# MRCS-Tortoise-to-MP-Adapter.net
KiCad netlist of a schematic drawn in EAGLE
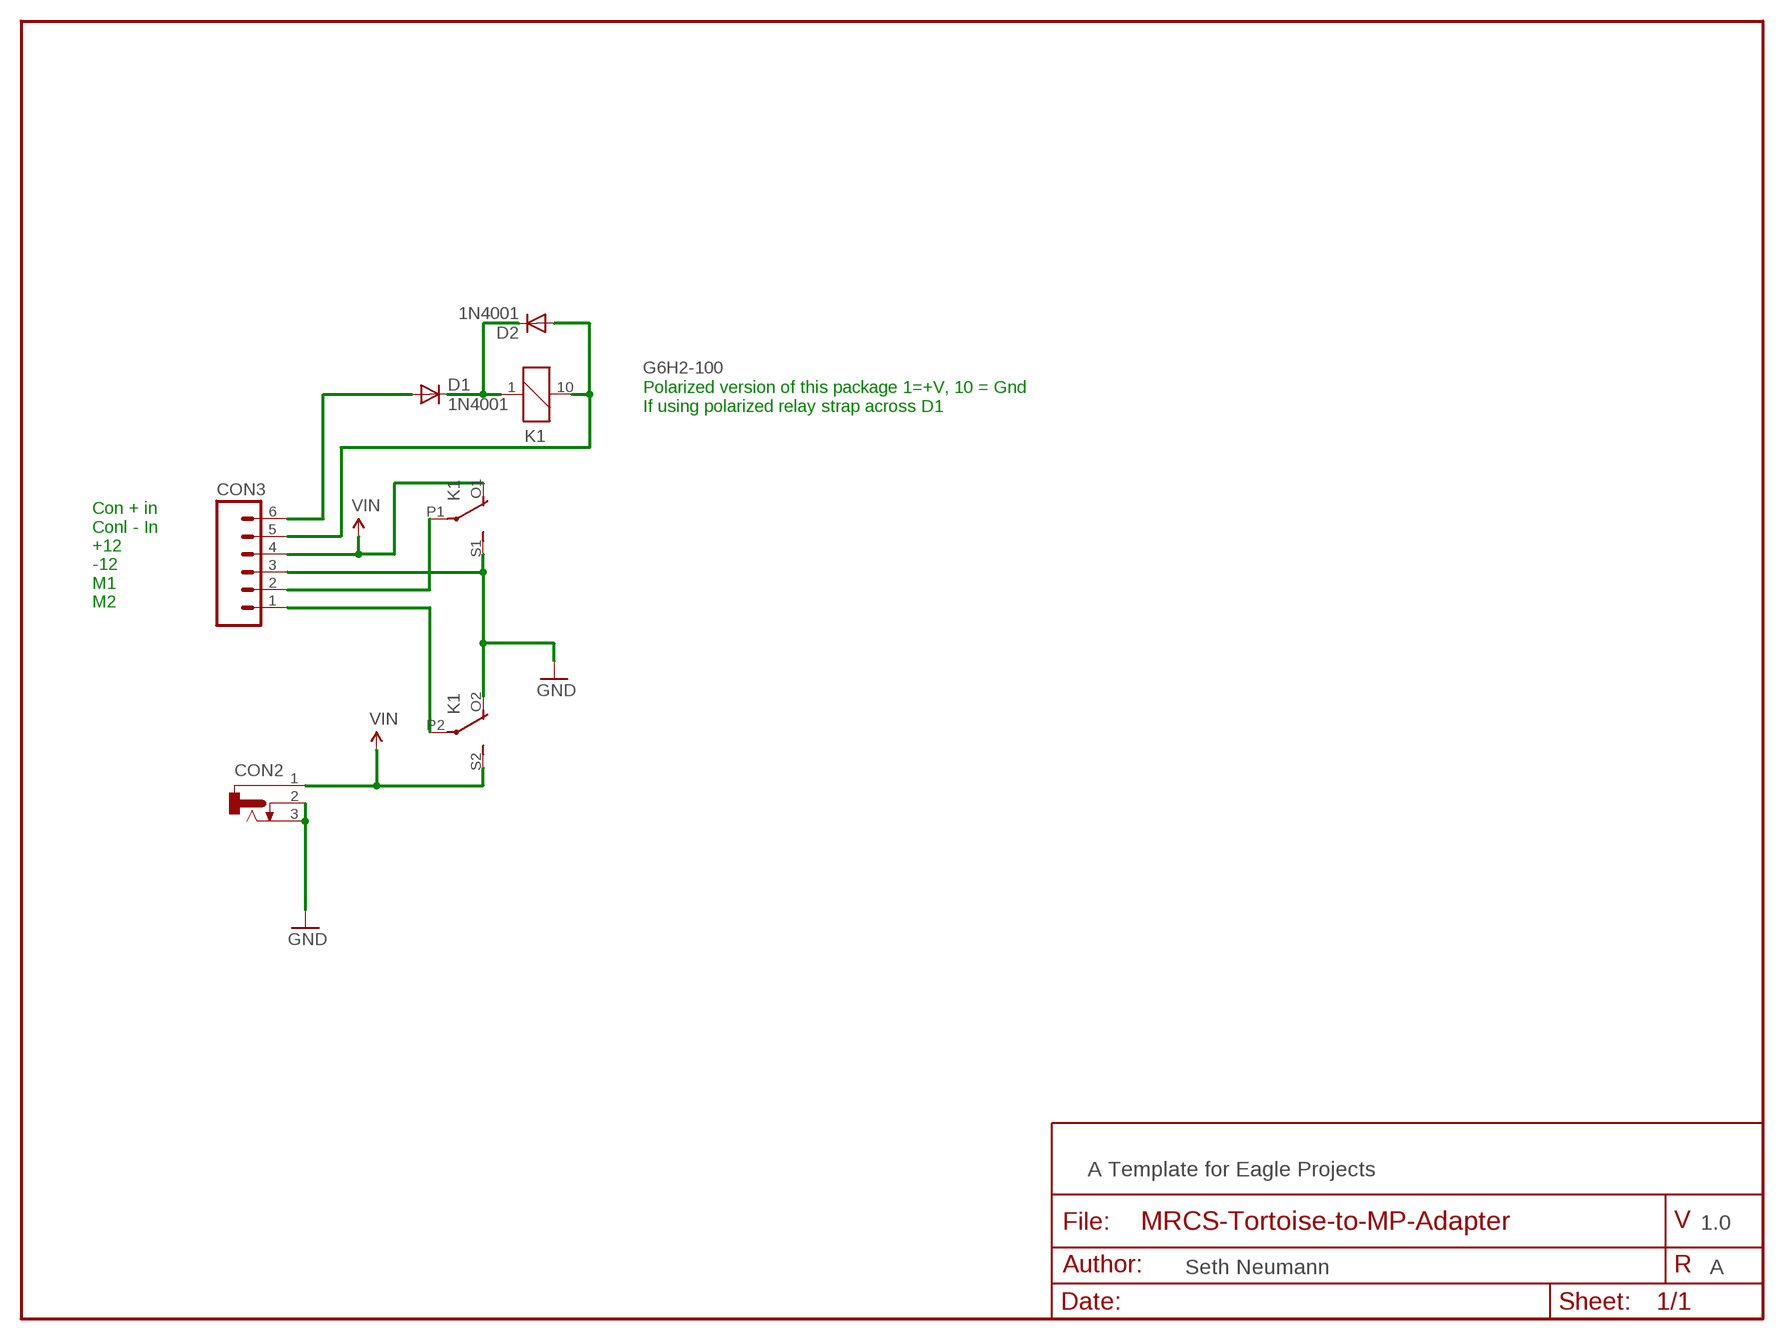
[diagram p0: schematic, sheet 1]

(export (version "E")
  (design (tool "Eeschema 10.0.6"))
  (components
    (comp (ref "CON2")
      (value "CONNECTOR-DC-POWER-RA")
      (footprint "eagle-import:DCJ0202")
      (libsource (lib "eagle-import") (part "CONNECTOR-DC-POWER-RA"))
    )
    (comp (ref "CON3")
      (value "CONNECTOR-M063.5MM-6")
      (footprint "eagle-import:SCREWTERMINAL-3.5MM-6")
      (libsource (lib "eagle-import") (part "CONNECTOR-M063.5MM-6"))
    )
    (comp (ref "D1")
      (value "1N4001")
      (footprint "eagle-import:DIODE-1N4001")
      (libsource (lib "eagle-import") (part "DIODEPTH"))
    )
    (comp (ref "D2")
      (value "1N4001")
      (footprint "eagle-import:DIODE-1N4001")
      (libsource (lib "eagle-import") (part "DIODEPTH"))
    )
    (comp (ref "K1")
      (value "G6H2-100")
      (footprint "eagle-import:G6H2-100")
      (libsource (lib "eagle-import") (part "G6H2-100"))
    )
  )
  (nets
    (net (code "1") (name "GND") (class "Default")
      (node (ref "CON2") (pin "2") (pinfunction "2_2") (pintype "passive"))
      (node (ref "CON2") (pin "3") (pinfunction "3_3") (pintype "passive"))
      (node (ref "CON3") (pin "3") (pinfunction "3_3") (pintype "passive"))
      (node (ref "K1") (pin "O2") (pinfunction "O_O2") (pintype "passive"))
      (node (ref "K1") (pin "S1") (pinfunction "S_S1") (pintype "passive"))
    )
    (net (code "2") (name "Net-(CON3-Pad6)") (class "Default")
      (node (ref "CON3") (pin "6") (pinfunction "6_6") (pintype "passive"))
      (node (ref "D1") (pin "A") (pinfunction "A_A") (pintype "passive"))
    )
    (net (code "3") (name "Net-(D1-PadC)") (class "Default")
      (node (ref "D1") (pin "C") (pinfunction "C_C") (pintype "passive"))
      (node (ref "D2") (pin "C") (pinfunction "C_C") (pintype "passive"))
      (node (ref "K1") (pin "1") (pinfunction "1_1") (pintype "passive"))
    )
    (net (code "4") (name "Net-(K1A-2)") (class "Default")
      (node (ref "CON3") (pin "5") (pinfunction "5_5") (pintype "passive"))
      (node (ref "D2") (pin "A") (pinfunction "A_A") (pintype "passive"))
      (node (ref "K1") (pin "10") (pinfunction "2_10") (pintype "passive"))
    )
    (net (code "5") (name "Net-(K1B-P)") (class "Default")
      (node (ref "CON3") (pin "2") (pinfunction "2_2") (pintype "passive"))
      (node (ref "K1") (pin "P1") (pinfunction "P_P1") (pintype "passive"))
    )
    (net (code "6") (name "Net-(K1C-P)") (class "Default")
      (node (ref "CON3") (pin "1") (pinfunction "1_1") (pintype "passive"))
      (node (ref "K1") (pin "P2") (pinfunction "P_P2") (pintype "passive"))
    )
    (net (code "7") (name "VIN") (class "Default")
      (node (ref "CON2") (pin "1") (pinfunction "1_1") (pintype "passive"))
      (node (ref "CON3") (pin "4") (pinfunction "4_4") (pintype "passive"))
      (node (ref "K1") (pin "O1") (pinfunction "O_O1") (pintype "passive"))
      (node (ref "K1") (pin "S2") (pinfunction "S_S2") (pintype "passive"))
    )
  )
)
